# 3_amplifier.net
KiCad netlist of a schematic drawn in Altium Designer
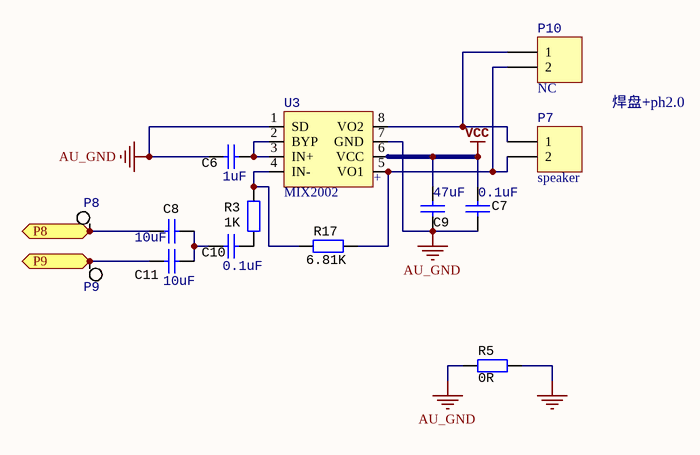
[diagram p0: 3 amplifier.SchDoc]

(export (version "E")
  (design (tool "Eeschema 10.0.6"))
  (components
    (comp (ref "C6")
      (value "1uF")
      (footprint "0402")
      (description "CAP, CERM, 0.01uF, 100V, +/-5%, X7R, 0603")
      (fields (field (name "PARTNUMBER") "06031C103JAT2A") (field (name "MANUFACTURER") "AVX"))
      (libsource (lib "03.常用器件") (part "CAP1_npol"))
    )
    (comp (ref "C7")
      (value "0.1uF")
      (footprint "0402")
      (description "CAP, CERM, 0.01uF, 100V, +/-5%, X7R, 0603")
      (fields (field (name "PARTNUMBER") "06031C103JAT2A") (field (name "MANUFACTURER") "AVX"))
      (libsource (lib "03.常用器件") (part "CAP1_npol"))
    )
    (comp (ref "C8")
      (value "10uF")
      (footprint "0603")
      (description "CAP, CERM, 0.01uF, 100V, +/-5%, X7R, 0603")
      (fields (field (name "PARTNUMBER") "06031C103JAT2A") (field (name "MANUFACTURER") "AVX"))
      (libsource (lib "03.常用器件") (part "CAP1_npol"))
    )
    (comp (ref "C9")
      (value "47uF")
      (footprint "0805")
      (description "CAP, CERM, 0.01uF, 100V, +/-5%, X7R, 0603")
      (fields (field (name "PARTNUMBER") "06031C103JAT2A") (field (name "MANUFACTURER") "AVX"))
      (libsource (lib "03.常用器件") (part "CAP1_npol"))
    )
    (comp (ref "C10")
      (value "0.1uF")
      (footprint "0402")
      (description "CAP, CERM, 0.01uF, 100V, +/-5%, X7R, 0603")
      (fields (field (name "PARTNUMBER") "06031C103JAT2A") (field (name "MANUFACTURER") "AVX"))
      (libsource (lib "03.常用器件") (part "CAP1_npol"))
    )
    (comp (ref "C11")
      (value "10uF")
      (footprint "0603")
      (description "CAP, CERM, 0.01uF, 100V, +/-5%, X7R, 0603")
      (fields (field (name "PARTNUMBER") "06031C103JAT2A") (field (name "MANUFACTURER") "AVX"))
      (libsource (lib "03.常用器件") (part "CAP1_npol"))
    )
    (comp (ref "P7")
      (value "speaker")
      (footprint "焊盘")
      (description "Header, 2-Pin")
      (fields (field (name "PUBLISHER") "Altium Limited"))
      (libsource (lib "Miscellaneous Connectors") (part "Header 2"))
    )
    (comp (ref "P8")
      (value "~")
      (footprint "测试点")
      (description "Test Point")
      (libsource (lib "my_Schlib") (part "TP"))
    )
    (comp (ref "P9")
      (value "~")
      (footprint "测试点")
      (description "Test Point")
      (libsource (lib "my_Schlib") (part "TP"))
    )
    (comp (ref "P10")
      (value "NC")
      (footprint "2PIN/2.0MM座子")
      (description "Header, 2-Pin")
      (fields (field (name "PUBLISHER") "Altium Limited"))
      (libsource (lib "Miscellaneous Connectors") (part "Header 2"))
    )
    (comp (ref "R3")
      (value "1K")
      (footprint "0402")
      (description "RES, 1.0k ohm, 5%, 0.1W, 0603")
      (fields
        (field (name "PARTNUMBER") "RC0603JR-071KL")
        (field (name "MANUFACTURER") "Yageo America")
        (field (name "PUBLISHER") "Texas Instruments")
      )
      (libsource (lib "03.常用器件") (part "RES1"))
    )
    (comp (ref "R5")
      (value "0R")
      (footprint "0402")
      (description "RES, 1.0k ohm, 5%, 0.1W, 0603")
      (fields
        (field (name "PARTNUMBER") "RC0603JR-071KL")
        (field (name "MANUFACTURER") "Yageo America")
        (field (name "PUBLISHER") "Texas Instruments")
      )
      (libsource (lib "") (part "RES1_2"))
    )
    (comp (ref "R17")
      (value "6.81K")
      (footprint "0402")
      (description "RES, 1.0k ohm, 5%, 0.1W, 0603")
      (fields
        (field (name "PARTNUMBER") "RC0603JR-071KL")
        (field (name "MANUFACTURER") "Yageo America")
        (field (name "PUBLISHER") "Texas Instruments")
      )
      (libsource (lib "") (part "RES1_1"))
    )
    (comp (ref "U3") (value "MIX2002") (footprint "SOP-8") (libsource (lib "Schlib1") (part "MIX2002")))
  )
  (nets
    (net (code "1") (name "/P8") (class "Default")
      (node (ref "C8") (pin "2") (pinfunction "2_2") (pintype "passive"))
      (node (ref "P8") (pin "1") (pinfunction "1_1") (pintype "passive"))
    )
    (net (code "2") (name "/P9") (class "Default")
      (node (ref "C11") (pin "2") (pinfunction "2_2") (pintype "passive"))
      (node (ref "P9") (pin "1") (pinfunction "1_1") (pintype "passive"))
    )
    (net (code "3") (name "<NO NET>") (class "Default")
      (node (ref "R5") (pin "1") (pinfunction "1_1") (pintype "passive"))
    )
    (net (code "4") (name "AU_GND") (class "Default")
      (node (ref "C6") (pin "1") (pinfunction "1_1") (pintype "passive"))
      (node (ref "C7") (pin "2") (pinfunction "2_2") (pintype "passive"))
      (node (ref "C9") (pin "2") (pinfunction "2_2") (pintype "passive"))
      (node (ref "R5") (pin "2") (pinfunction "2_2") (pintype "passive"))
      (node (ref "U3") (pin "1") (pinfunction "SD_1") (pintype "passive"))
      (node (ref "U3") (pin "7") (pinfunction "GND_7") (pintype "passive"))
    )
    (net (code "5") (name "Net-(C10-Pad1)") (class "Default")
      (node (ref "C10") (pin "1") (pinfunction "1_1") (pintype "passive"))
      (node (ref "C11") (pin "1") (pinfunction "1_1") (pintype "passive"))
      (node (ref "C8") (pin "1") (pinfunction "1_1") (pintype "passive"))
    )
    (net (code "6") (name "Net-(C10-Pad2)") (class "Default")
      (node (ref "C10") (pin "2") (pinfunction "2_2") (pintype "passive"))
      (node (ref "R3") (pin "1") (pinfunction "1_1") (pintype "passive"))
    )
    (net (code "7") (name "Net-(U3-BYP)") (class "Default")
      (node (ref "C6") (pin "2") (pinfunction "2_2") (pintype "passive"))
      (node (ref "U3") (pin "2") (pinfunction "BYP_2") (pintype "passive"))
      (node (ref "U3") (pin "3") (pinfunction "IN+_3") (pintype "passive"))
    )
    (net (code "8") (name "Net-(U3-IN-)") (class "Default")
      (node (ref "R17") (pin "1") (pinfunction "1_1") (pintype "passive"))
      (node (ref "R3") (pin "2") (pinfunction "2_2") (pintype "passive"))
      (node (ref "U3") (pin "4") (pinfunction "IN-_4") (pintype "passive"))
    )
    (net (code "9") (name "Net-(U3-VO1)") (class "Default")
      (node (ref "P10") (pin "2") (pinfunction "2_2") (pintype "passive"))
      (node (ref "P7") (pin "2") (pinfunction "2_2") (pintype "passive"))
      (node (ref "R17") (pin "2") (pinfunction "2_2") (pintype "passive"))
      (node (ref "U3") (pin "5") (pinfunction "VO1_5") (pintype "passive"))
    )
    (net (code "10") (name "Net-(U3-VO2)") (class "Default")
      (node (ref "P10") (pin "1") (pinfunction "1_1") (pintype "passive"))
      (node (ref "P7") (pin "1") (pinfunction "1_1") (pintype "passive"))
      (node (ref "U3") (pin "8") (pinfunction "VO2_8") (pintype "passive"))
    )
    (net (code "11") (name "VCC") (class "Default")
      (node (ref "C7") (pin "1") (pinfunction "1_1") (pintype "passive"))
      (node (ref "C9") (pin "1") (pinfunction "1_1") (pintype "passive"))
      (node (ref "U3") (pin "6") (pinfunction "VCC_6") (pintype "passive"))
    )
  )
)
